# JackNoiDenChop.net
KiCad netlist of a schematic drawn in Altium Designer
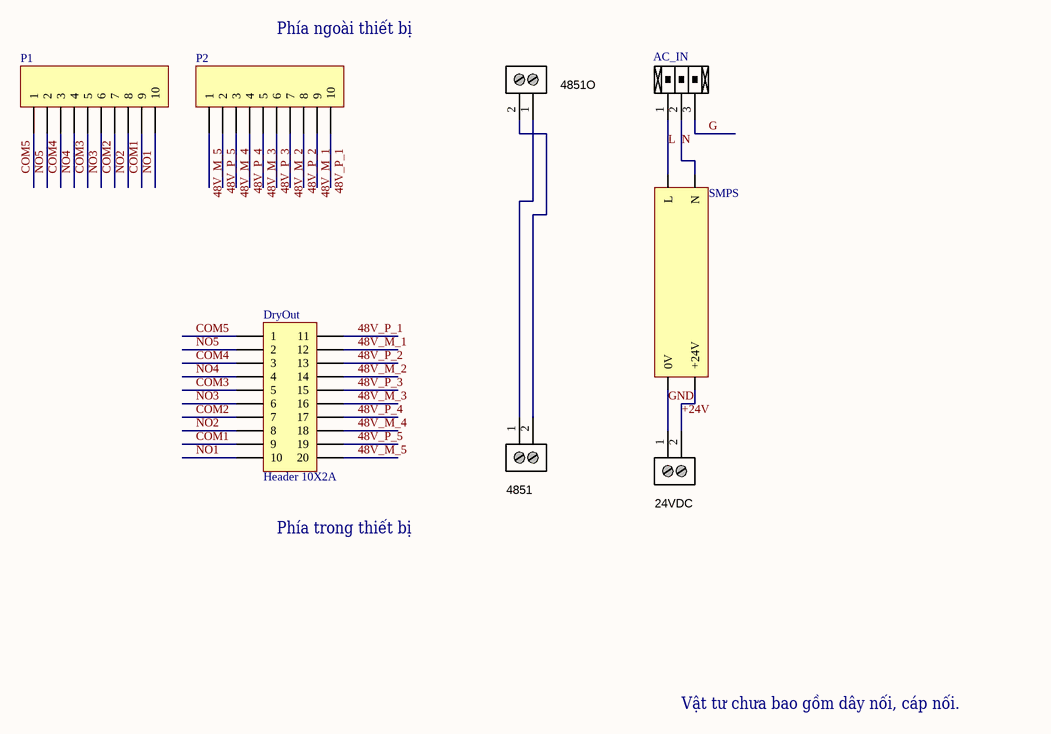
[diagram p0: JackNoiDenChop.SchDoc]

(export (version "E")
  (design (tool "Eeschema 10.0.6"))
  (components
    (comp (ref "24VDC")
      (value "Giắc xanh 5.08mm")
      (footprint "2P_PCB1")
      (description "Terminal Block Screw Type THT 2-Position 3.81mm pitch")
      (libsource (lib "PBL - Connectors") (part "2P_ScrewTerm_90S_3.81MM"))
    )
    (comp (ref "4851")
      (value "Giắc xanh 5.08mm")
      (footprint "2P_PCB1")
      (description "Terminal Block Screw Type THT 2-Position 3.81mm pitch")
      (libsource (lib "PBL - Connectors") (part "2P_ScrewTerm_90S_3.81MM"))
    )
    (comp (ref "4851O")
      (value "Giắc xanh 5.08mm")
      (footprint "2P_PCB1")
      (description "Terminal Block Screw Type THT 2-Position 3.81mm pitch")
      (libsource (lib "") (part "2P_ScrewTerm_90S_3.81MM_1"))
    )
    (comp (ref "AC_IN")
      (value "Giăc xanh 3 chân, khoảng cách chân 200mil/5.08mm")
      (footprint "hayqua:3P_ScrewTerm_200mil")
      (description "Terminal Block THT 3-Position header 5.08mm/200mil pitch")
      (libsource (lib "Tuan") (part "3P_ScrewTerm_200mil"))
    )
    (comp (ref "DryOut")
      (value "Header 10X2A")
      (footprint "heromap:HDR2X10_CEN")
      (description "Header, 10-Pin, Dual row")
      (fields (field (name "PUBLISHER") "Altium Limited"))
      (libsource (lib "heromap") (part "Header 10X2A"))
    )
    (comp (ref "P1")
      (value "Giắc xanh 10 chân, khoảng cách chân 5.08mm")
      (footprint "hayqua:10P_200mil")
      (description "Header, 10-Pin")
      (fields (field (name "PUBLISHER") "Altium Limited"))
      (libsource (lib "Miscellaneous Connectors") (part "MHDR1X10"))
    )
    (comp (ref "P2")
      (value "Giắc xanh 10 chân, khoảng cách chân 5.08mm")
      (footprint "hayqua:10P_200mil")
      (description "Header, 10-Pin")
      (fields (field (name "PUBLISHER") "Altium Limited"))
      (libsource (lib "Miscellaneous Connectors") (part "MHDR1X10"))
    )
    (comp (ref "SMPS")
      (value "Bộ nguồn xung AC-DC 24V/1.3A, MEANWELL IRM30-24")
      (libsource (lib "DenChop400V") (part "SMPS"))
    )
  )
  (nets
    (net (code "1") (name "/+24V") (class "Default")
      (node (ref "24VDC") (pin "2") (pinfunction "2_2") (pintype "passive"))
      (node (ref "SMPS") (pin "3") (pinfunction "+24V_3") (pintype "passive"))
    )
    (net (code "2") (name "/48V_M_1") (class "Default")
      (node (ref "DryOut") (pin "12") (pinfunction "12_12") (pintype "passive"))
      (node (ref "P2") (pin "9") (pinfunction "9_9") (pintype "passive"))
    )
    (net (code "3") (name "/48V_M_2") (class "Default")
      (node (ref "DryOut") (pin "14") (pinfunction "14_14") (pintype "passive"))
      (node (ref "P2") (pin "7") (pinfunction "7_7") (pintype "passive"))
    )
    (net (code "4") (name "/48V_M_3") (class "Default")
      (node (ref "DryOut") (pin "16") (pinfunction "16_16") (pintype "passive"))
      (node (ref "P2") (pin "5") (pinfunction "5_5") (pintype "passive"))
    )
    (net (code "5") (name "/48V_M_4") (class "Default")
      (node (ref "DryOut") (pin "18") (pinfunction "18_18") (pintype "passive"))
      (node (ref "P2") (pin "3") (pinfunction "3_3") (pintype "passive"))
    )
    (net (code "6") (name "/48V_M_5") (class "Default")
      (node (ref "DryOut") (pin "20") (pinfunction "20_20") (pintype "passive"))
      (node (ref "P2") (pin "1") (pinfunction "1_1") (pintype "passive"))
    )
    (net (code "7") (name "/48V_P_1") (class "Default")
      (node (ref "DryOut") (pin "11") (pinfunction "11_11") (pintype "passive"))
      (node (ref "P2") (pin "10") (pinfunction "10_10") (pintype "passive"))
    )
    (net (code "8") (name "/48V_P_2") (class "Default")
      (node (ref "DryOut") (pin "13") (pinfunction "13_13") (pintype "passive"))
      (node (ref "P2") (pin "8") (pinfunction "8_8") (pintype "passive"))
    )
    (net (code "9") (name "/48V_P_3") (class "Default")
      (node (ref "DryOut") (pin "15") (pinfunction "15_15") (pintype "passive"))
      (node (ref "P2") (pin "6") (pinfunction "6_6") (pintype "passive"))
    )
    (net (code "10") (name "/48V_P_4") (class "Default")
      (node (ref "DryOut") (pin "17") (pinfunction "17_17") (pintype "passive"))
      (node (ref "P2") (pin "4") (pinfunction "4_4") (pintype "passive"))
    )
    (net (code "11") (name "/48V_P_5") (class "Default")
      (node (ref "DryOut") (pin "19") (pinfunction "19_19") (pintype "passive"))
      (node (ref "P2") (pin "2") (pinfunction "2_2") (pintype "passive"))
    )
    (net (code "12") (name "/COM1") (class "Default")
      (node (ref "DryOut") (pin "9") (pinfunction "9_9") (pintype "passive"))
      (node (ref "P1") (pin "9") (pinfunction "9_9") (pintype "passive"))
    )
    (net (code "13") (name "/COM2") (class "Default")
      (node (ref "DryOut") (pin "7") (pinfunction "7_7") (pintype "passive"))
      (node (ref "P1") (pin "7") (pinfunction "7_7") (pintype "passive"))
    )
    (net (code "14") (name "/COM3") (class "Default")
      (node (ref "DryOut") (pin "5") (pinfunction "5_5") (pintype "passive"))
      (node (ref "P1") (pin "5") (pinfunction "5_5") (pintype "passive"))
    )
    (net (code "15") (name "/COM4") (class "Default")
      (node (ref "DryOut") (pin "3") (pinfunction "3_3") (pintype "passive"))
      (node (ref "P1") (pin "3") (pinfunction "3_3") (pintype "passive"))
    )
    (net (code "16") (name "/COM5") (class "Default")
      (node (ref "DryOut") (pin "1") (pinfunction "1_1") (pintype "passive"))
      (node (ref "P1") (pin "1") (pinfunction "1_1") (pintype "passive"))
    )
    (net (code "17") (name "/G") (class "Default")
      (node (ref "AC_IN") (pin "3") (pinfunction "3_3") (pintype "passive"))
    )
    (net (code "18") (name "/GND") (class "Default")
      (node (ref "24VDC") (pin "1") (pinfunction "1_1") (pintype "passive"))
      (node (ref "SMPS") (pin "4") (pinfunction "0V_4") (pintype "passive"))
    )
    (net (code "19") (name "/L") (class "Default")
      (node (ref "AC_IN") (pin "1") (pinfunction "1_1") (pintype "passive"))
      (node (ref "SMPS") (pin "2") (pinfunction "L_2") (pintype "passive"))
    )
    (net (code "20") (name "/N") (class "Default")
      (node (ref "AC_IN") (pin "2") (pinfunction "2_2") (pintype "passive"))
      (node (ref "SMPS") (pin "1") (pinfunction "N_1") (pintype "passive"))
    )
    (net (code "21") (name "/NO1") (class "Default")
      (node (ref "DryOut") (pin "10") (pinfunction "10_10") (pintype "passive"))
      (node (ref "P1") (pin "10") (pinfunction "10_10") (pintype "passive"))
    )
    (net (code "22") (name "/NO2") (class "Default")
      (node (ref "DryOut") (pin "8") (pinfunction "8_8") (pintype "passive"))
      (node (ref "P1") (pin "8") (pinfunction "8_8") (pintype "passive"))
    )
    (net (code "23") (name "/NO3") (class "Default")
      (node (ref "DryOut") (pin "6") (pinfunction "6_6") (pintype "passive"))
      (node (ref "P1") (pin "6") (pinfunction "6_6") (pintype "passive"))
    )
    (net (code "24") (name "/NO4") (class "Default")
      (node (ref "DryOut") (pin "4") (pinfunction "4_4") (pintype "passive"))
      (node (ref "P1") (pin "4") (pinfunction "4_4") (pintype "passive"))
    )
    (net (code "25") (name "/NO5") (class "Default")
      (node (ref "DryOut") (pin "2") (pinfunction "2_2") (pintype "passive"))
      (node (ref "P1") (pin "2") (pinfunction "2_2") (pintype "passive"))
    )
    (net (code "26") (name "Net-(4851-Pad1)") (class "Default")
      (node (ref "4851") (pin "1") (pinfunction "1_1") (pintype "passive"))
      (node (ref "4851O") (pin "1") (pinfunction "1_1") (pintype "passive"))
    )
    (net (code "27") (name "Net-(4851-Pad2)") (class "Default")
      (node (ref "4851") (pin "2") (pinfunction "2_2") (pintype "passive"))
      (node (ref "4851O") (pin "2") (pinfunction "2_2") (pintype "passive"))
    )
  )
)
